# LED_Power_Ind.net
KiCad netlist of a schematic drawn in Altium Designer
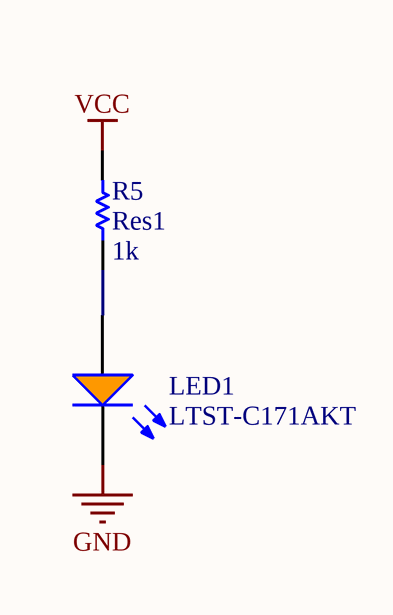
[diagram p0: LED_Power_Ind.SchDoc]

(export (version "E")
  (design (tool "Eeschema 10.0.6"))
  (components
    (comp (ref "LED1")
      (value "LTST-C171AKT")
      (footprint "LTST-C171AKT_V")
      (description "LED Uni-Color Orange, 100 mW, 120 mA, -55 to 85 degC, 2-Pin SMD, RoHS, Tape and Reel")
      (fields (field (name "MANUFACTURER") "Lite-On"))
      (libsource (lib "Altium Content Vault") (part "CMP-1674-00004-5"))
    )
    (comp (ref "R5")
      (value "Res1")
      (footprint "6-0805_L")
      (description "Resistor")
      (fields (field (name "ALTIUM_VALUE") "1k") (field (name "PUBLISHER") "Altium Limited"))
      (libsource (lib "Miscellaneous Devices") (part "Res1"))
    )
  )
  (nets
    (net (code "1") (name "GND") (class "Default")
      (node (ref "LED1") (pin "2") (pinfunction "K_2") (pintype "passive"))
    )
    (net (code "2") (name "Net-(LED1-A)") (class "Default")
      (node (ref "LED1") (pin "1") (pinfunction "A_1") (pintype "passive"))
      (node (ref "R5") (pin "1") (pinfunction "1_1") (pintype "passive"))
    )
    (net (code "3") (name "VCC") (class "Default")
      (node (ref "R5") (pin "2") (pinfunction "2_2") (pintype "passive"))
    )
  )
)
